# TBarLedWindow.net
KiCad netlist of a schematic drawn in Altium Designer
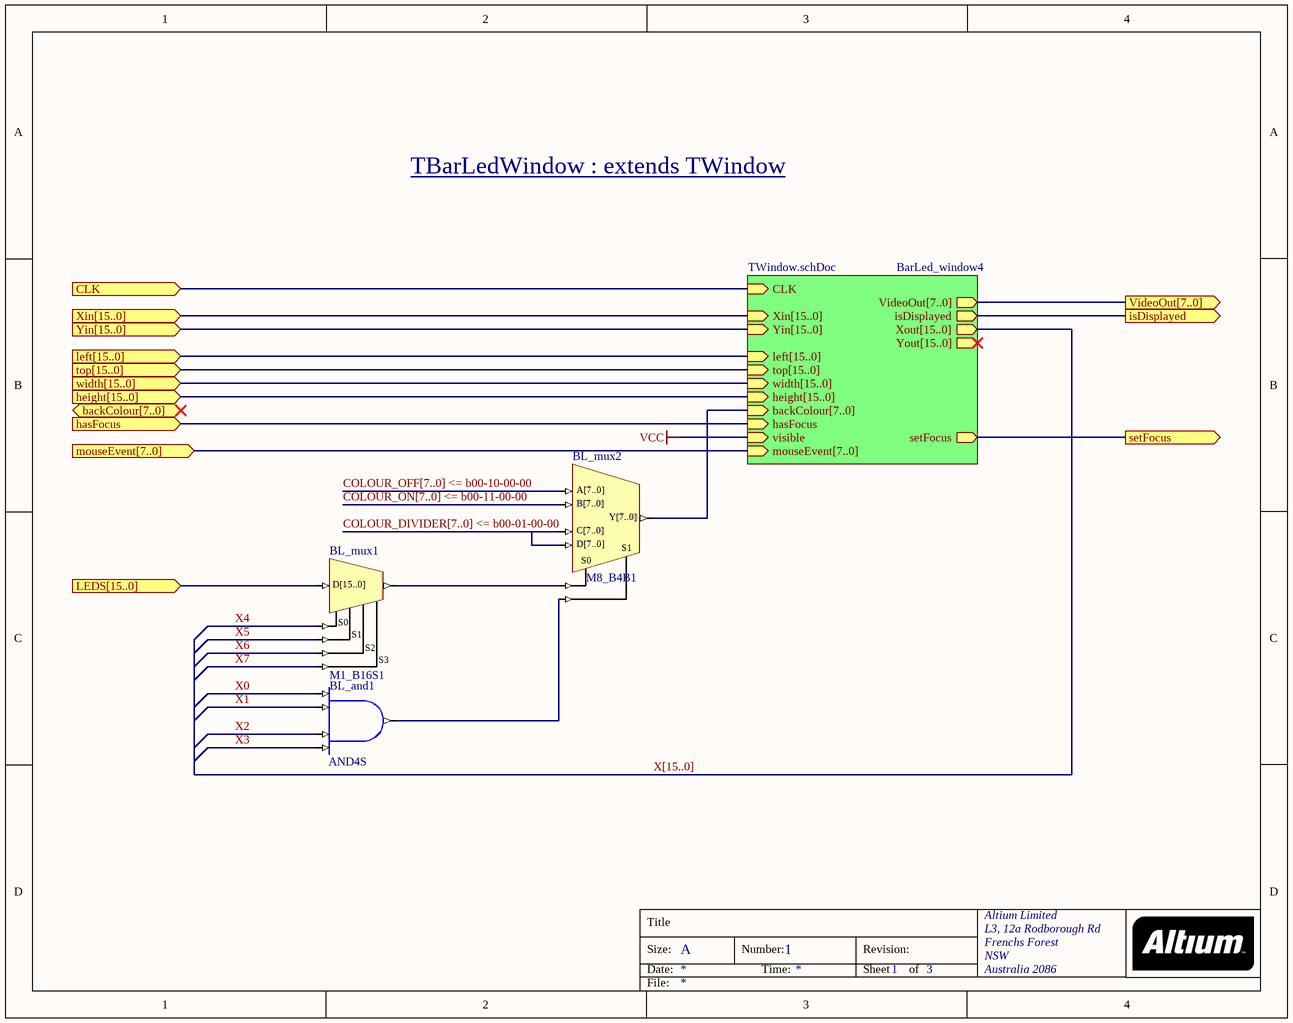
[diagram p0: TBarLedWindow.schDOC]

(export (version "E")
  (design (tool "Eeschema 10.0.6"))
  (components
    (comp (ref "BL_and1")
      (value "AND4S")
      (description "4-Input AND Gate, Single Pin Version")
      (fields (field (name "PUBLISHER") "Altium Limited"))
      (libsource (lib "FPGA Generic") (part "AND4S"))
    )
    (comp (ref "BL_mux1")
      (value "M1_B16S1")
      (description "1x16-Bit Bus to 1x1-Single Wire Multiplexer")
      (fields (field (name "PUBLISHER") "Altium Limited"))
      (libsource (lib "FPGA Generic") (part "M1_B16S1"))
    )
    (comp (ref "BL_mux2")
      (value "M8_B4B1")
      (description "4x8-Bit Bus to 1x8-Bit Bus Multiplexer")
      (fields (field (name "PUBLISHER") "Altium Limited"))
      (libsource (lib "FPGA Generic") (part "M8_B4B1"))
    )
  )
  (nets
    (net (code "146") (name "/COLOUR_DIVIDER[7..0] <= b00-01-00-00") (class "Default")
      (node (ref "BL_mux2") (pin "C[7..0]") (pinfunction "C[7..0]_C[7..0]") (pintype "input"))
    )
    (net (code "147") (name "/COLOUR_OFF[7..0] <= b00-10-00-00") (class "Default")
      (node (ref "BL_mux2") (pin "A[7..0]") (pinfunction "A[7..0]_A[7..0]") (pintype "input"))
    )
    (net (code "148") (name "/COLOUR_ON[7..0] <= b00-11-00-00") (class "Default")
      (node (ref "BL_mux2") (pin "B[7..0]") (pinfunction "B[7..0]_B[7..0]") (pintype "input"))
    )
    (net (code "149") (name "/LEDS[15..0]") (class "Default")
      (node (ref "BL_mux1") (pin "D[15..0]") (pinfunction "D[15..0]_D[15..0]") (pintype "input"))
    )
    (net (code "151") (name "/X0") (class "Default")
      (node (ref "BL_and1") (pin "I0") (pinfunction "I0_I0") (pintype "input"))
    )
    (net (code "152") (name "/X1") (class "Default")
      (node (ref "BL_and1") (pin "I1") (pinfunction "I1_I1") (pintype "input"))
    )
    (net (code "153") (name "/X2") (class "Default")
      (node (ref "BL_and1") (pin "I2") (pinfunction "I2_I2") (pintype "input"))
    )
    (net (code "154") (name "/X3") (class "Default")
      (node (ref "BL_and1") (pin "I3") (pinfunction "I3_I3") (pintype "input"))
    )
    (net (code "155") (name "/X4") (class "Default")
      (node (ref "BL_mux1") (pin "S0") (pinfunction "S0_S0") (pintype "input"))
    )
    (net (code "156") (name "/X5") (class "Default")
      (node (ref "BL_mux1") (pin "S1") (pinfunction "S1_S1") (pintype "input"))
    )
    (net (code "157") (name "/X6") (class "Default")
      (node (ref "BL_mux1") (pin "S2") (pinfunction "S2_S2") (pintype "input"))
    )
    (net (code "158") (name "/X7") (class "Default")
      (node (ref "BL_mux1") (pin "S3") (pinfunction "S3_S3") (pintype "input"))
    )
    (net (code "164") (name "/backColour[7..0]_1") (class "Default")
      (node (ref "BL_mux2") (pin "Y[7..0]") (pinfunction "Y[7..0]_Y[7..0]") (pintype "output"))
    )
    (net (code "173") (name "Net-(BL_and1-PadO)") (class "Default")
      (node (ref "BL_and1") (pin "O") (pinfunction "O_O") (pintype "output"))
      (node (ref "BL_mux2") (pin "S1") (pinfunction "S1_S1") (pintype "input"))
    )
    (net (code "174") (name "Net-(BL_mux1-PadO)") (class "Default")
      (node (ref "BL_mux1") (pin "O") (pinfunction "O_O") (pintype "output"))
      (node (ref "BL_mux2") (pin "S0") (pinfunction "S0_S0") (pintype "input"))
    )
    (net (code "176") (name "unconnected-(BL_mux2-PadD[7..0])") (class "Default")
      (node (ref "BL_mux2") (pin "D[7..0]") (pinfunction "D[7..0]_D[7..0]") (pintype "input"))
    )
  )
)
